# ESP8266-ILI9341-V003_2.net
KiCad netlist of a schematic drawn in EAGLE
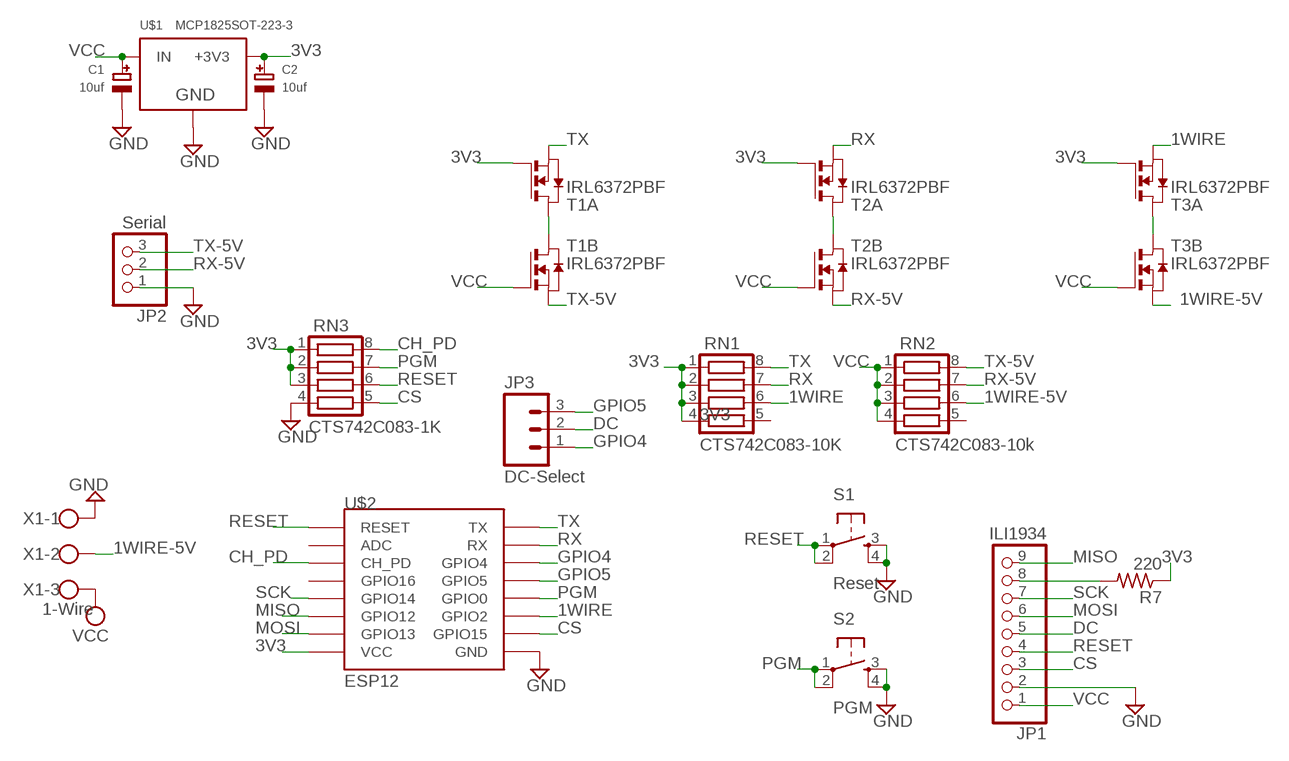
[diagram p0: schematic, sheet 1]

(export (version "E")
  (design (tool "Eeschema 10.0.6"))
  (components
    (comp (ref "C1")
      (value "10uf")
      (footprint "eagle-import:EIA3216-18_A-R")
      (libsource (lib "eagle-import") (part "CAP_TANTALUMA/3216_REFLOW"))
    )
    (comp (ref "C2")
      (value "10uf")
      (footprint "eagle-import:EIA3216-18_A-R")
      (libsource (lib "eagle-import") (part "CAP_TANTALUMA/3216_REFLOW"))
    )
    (comp (ref "JP1")
      (value "ILI1934")
      (footprint "eagle-import:1X09-BIG")
      (libsource (lib "eagle-import") (part "PINHD-1X9"))
    )
    (comp (ref "JP2")
      (value "Serial")
      (footprint "eagle-import:1X03")
      (libsource (lib "eagle-import") (part "PINHD-1X3"))
    )
    (comp (ref "JP3")
      (value "DC-Select")
      (footprint "eagle-import:1X03")
      (libsource (lib "eagle-import") (part "M03PTH"))
    )
    (comp (ref "R7")
      (value "220")
      (footprint "eagle-import:M1206")
      (libsource (lib "eagle-import") (part "R-US_M1206"))
    )
    (comp (ref "RN1")
      (value "CTS742C083-10K")
      (footprint "eagle-import:CTS742C083")
      (libsource (lib "eagle-import") (part "CTS742C083"))
    )
    (comp (ref "RN2")
      (value "CTS742C083-10k")
      (footprint "eagle-import:CTS742C083")
      (libsource (lib "eagle-import") (part "CTS742C083"))
    )
    (comp (ref "RN3")
      (value "CTS742C083-1K")
      (footprint "eagle-import:CTS742C083")
      (libsource (lib "eagle-import") (part "CTS742C083"))
    )
    (comp (ref "S1")
      (value "Reset")
      (footprint "eagle-import:TACTILE-PTH")
      (libsource (lib "eagle-import") (part "TAC_SWITCHPTH"))
    )
    (comp (ref "S2")
      (value "PGM")
      (footprint "eagle-import:TACTILE-PTH")
      (libsource (lib "eagle-import") (part "TAC_SWITCHPTH"))
    )
    (comp (ref "T1")
      (value "IRL6372PBF")
      (footprint "eagle-import:SO-8-DUAL")
      (libsource (lib "eagle-import") (part "IRL6372PBF"))
    )
    (comp (ref "T2")
      (value "IRL6372PBF")
      (footprint "eagle-import:SO-8-DUAL")
      (libsource (lib "eagle-import") (part "IRL6372PBF"))
    )
    (comp (ref "T3")
      (value "IRL6372PBF")
      (footprint "eagle-import:SO-8-DUAL")
      (libsource (lib "eagle-import") (part "IRL6372PBF"))
    )
    (comp (ref "U$1")
      (value "MCP1825SOT-223-3")
      (footprint "eagle-import:SOT-223")
      (libsource (lib "eagle-import") (part "MCP1825SOT-223-3"))
    )
    (comp (ref "U$2")
      (value "ESP12")
      (footprint "eagle-import:ESP12")
      (libsource (lib "eagle-import") (part "ESP12"))
    )
    (comp (ref "X1")
      (value "1-Wire")
      (footprint "eagle-import:W237-103")
      (fields (field (name "MPN") "237-103"))
      (libsource (lib "eagle-import") (part "W237-103"))
    )
  )
  (nets
    (net (code "1") (name "/1WIRE") (class "Default")
      (node (ref "RN1") (pin "6") (pinfunction "6_6") (pintype "passive"))
      (node (ref "T3") (pin "1") (pinfunction "S_1") (pintype "passive"))
      (node (ref "U$2") (pin "GPIO2") (pinfunction "GPIO2_GPIO2") (pintype "bidirectional"))
    )
    (net (code "2") (name "/1WIRE-5V") (class "Default")
      (node (ref "RN2") (pin "6") (pinfunction "6_6") (pintype "passive"))
      (node (ref "T3") (pin "3") (pinfunction "S_3") (pintype "passive"))
      (node (ref "X1") (pin "2") (pinfunction "KL_2") (pintype "passive"))
    )
    (net (code "3") (name "/3V3") (class "Default")
      (node (ref "C2") (pin "+") (pinfunction "+_+") (pintype "passive"))
      (node (ref "R7") (pin "1") (pinfunction "1_1") (pintype "passive"))
      (node (ref "RN1") (pin "1") (pinfunction "1_1") (pintype "passive"))
      (node (ref "RN1") (pin "2") (pinfunction "2_2") (pintype "passive"))
      (node (ref "RN1") (pin "3") (pinfunction "3_3") (pintype "passive"))
      (node (ref "RN1") (pin "4") (pinfunction "4_4") (pintype "passive"))
      (node (ref "RN3") (pin "1") (pinfunction "1_1") (pintype "passive"))
      (node (ref "RN3") (pin "2") (pinfunction "2_2") (pintype "passive"))
      (node (ref "RN3") (pin "3") (pinfunction "3_3") (pintype "passive"))
      (node (ref "T1") (pin "2") (pinfunction "G_2") (pintype "passive"))
      (node (ref "T2") (pin "2") (pinfunction "G_2") (pintype "passive"))
      (node (ref "T3") (pin "2") (pinfunction "G_2") (pintype "passive"))
      (node (ref "U$1") (pin "3") (pinfunction "+3V3_3") (pintype "power_in"))
      (node (ref "U$2") (pin "VCC") (pinfunction "VCC_VCC") (pintype "bidirectional"))
    )
    (net (code "4") (name "/CH_PD") (class "Default")
      (node (ref "RN3") (pin "8") (pinfunction "8_8") (pintype "passive"))
      (node (ref "U$2") (pin "CH_PD") (pinfunction "CH_PD_CH_PD") (pintype "bidirectional"))
    )
    (net (code "5") (name "/CS") (class "Default")
      (node (ref "JP1") (pin "3") (pinfunction "3_3") (pintype "passive"))
      (node (ref "RN3") (pin "5") (pinfunction "5_5") (pintype "passive"))
      (node (ref "U$2") (pin "GPIO15") (pinfunction "GPIO15_GPIO15") (pintype "bidirectional"))
    )
    (net (code "6") (name "/DC") (class "Default")
      (node (ref "JP1") (pin "5") (pinfunction "5_5") (pintype "passive"))
      (node (ref "JP3") (pin "2") (pinfunction "2_2") (pintype "passive"))
    )
    (net (code "7") (name "/GPIO4") (class "Default")
      (node (ref "JP3") (pin "1") (pinfunction "1_1") (pintype "passive"))
      (node (ref "U$2") (pin "GPIO4") (pinfunction "GPIO4_GPIO4") (pintype "bidirectional"))
    )
    (net (code "8") (name "/GPIO5") (class "Default")
      (node (ref "JP3") (pin "3") (pinfunction "3_3") (pintype "passive"))
      (node (ref "U$2") (pin "GPIO5") (pinfunction "GPIO5_GPIO5") (pintype "bidirectional"))
    )
    (net (code "9") (name "/MISO") (class "Default")
      (node (ref "JP1") (pin "9") (pinfunction "9_9") (pintype "passive"))
      (node (ref "U$2") (pin "GPIO12") (pinfunction "GPIO12_GPIO12") (pintype "bidirectional"))
    )
    (net (code "10") (name "/MOSI") (class "Default")
      (node (ref "JP1") (pin "6") (pinfunction "6_6") (pintype "passive"))
      (node (ref "U$2") (pin "GPIO13") (pinfunction "GPIO13_GPIO13") (pintype "bidirectional"))
    )
    (net (code "11") (name "/PGM") (class "Default")
      (node (ref "RN3") (pin "7") (pinfunction "7_7") (pintype "passive"))
      (node (ref "S2") (pin "1") (pinfunction "1_1") (pintype "passive"))
      (node (ref "S2") (pin "2") (pinfunction "2_2") (pintype "passive"))
      (node (ref "U$2") (pin "GPIO0") (pinfunction "GPIO0_GPIO0") (pintype "bidirectional"))
    )
    (net (code "12") (name "/RESET") (class "Default")
      (node (ref "JP1") (pin "4") (pinfunction "4_4") (pintype "passive"))
      (node (ref "RN3") (pin "6") (pinfunction "6_6") (pintype "passive"))
      (node (ref "S1") (pin "1") (pinfunction "1_1") (pintype "passive"))
      (node (ref "S1") (pin "2") (pinfunction "2_2") (pintype "passive"))
      (node (ref "U$2") (pin "RESET") (pinfunction "RESET_RESET") (pintype "bidirectional"))
    )
    (net (code "13") (name "/RX") (class "Default")
      (node (ref "RN1") (pin "7") (pinfunction "7_7") (pintype "passive"))
      (node (ref "T2") (pin "1") (pinfunction "S_1") (pintype "passive"))
      (node (ref "U$2") (pin "RX") (pinfunction "RX_RX") (pintype "bidirectional"))
    )
    (net (code "14") (name "/RX-5V") (class "Default")
      (node (ref "JP2") (pin "2") (pinfunction "2_2") (pintype "passive"))
      (node (ref "RN2") (pin "7") (pinfunction "7_7") (pintype "passive"))
      (node (ref "T2") (pin "3") (pinfunction "S_3") (pintype "passive"))
    )
    (net (code "15") (name "/SCK") (class "Default")
      (node (ref "JP1") (pin "7") (pinfunction "7_7") (pintype "passive"))
      (node (ref "U$2") (pin "GPIO14") (pinfunction "GPIO14_GPIO14") (pintype "bidirectional"))
    )
    (net (code "16") (name "/TX") (class "Default")
      (node (ref "RN1") (pin "8") (pinfunction "8_8") (pintype "passive"))
      (node (ref "T1") (pin "1") (pinfunction "S_1") (pintype "passive"))
      (node (ref "U$2") (pin "TX") (pinfunction "TX_TX") (pintype "bidirectional"))
    )
    (net (code "17") (name "/TX-5V") (class "Default")
      (node (ref "JP2") (pin "3") (pinfunction "3_3") (pintype "passive"))
      (node (ref "RN2") (pin "8") (pinfunction "8_8") (pintype "passive"))
      (node (ref "T1") (pin "3") (pinfunction "S_3") (pintype "passive"))
    )
    (net (code "18") (name "GND") (class "Default")
      (node (ref "C1") (pin "-") (pinfunction "-_-") (pintype "passive"))
      (node (ref "C2") (pin "-") (pinfunction "-_-") (pintype "passive"))
      (node (ref "JP1") (pin "2") (pinfunction "2_2") (pintype "passive"))
      (node (ref "JP2") (pin "1") (pinfunction "1_1") (pintype "passive"))
      (node (ref "RN3") (pin "4") (pinfunction "4_4") (pintype "passive"))
      (node (ref "S1") (pin "3") (pinfunction "3_3") (pintype "passive"))
      (node (ref "S1") (pin "4") (pinfunction "4_4") (pintype "passive"))
      (node (ref "S2") (pin "3") (pinfunction "3_3") (pintype "passive"))
      (node (ref "S2") (pin "4") (pinfunction "4_4") (pintype "passive"))
      (node (ref "U$1") (pin "2") (pinfunction "GND_2") (pintype "power_in"))
      (node (ref "U$2") (pin "GND") (pinfunction "GND_GND") (pintype "bidirectional"))
      (node (ref "X1") (pin "1") (pinfunction "KL_1") (pintype "passive"))
    )
    (net (code "19") (name "Net-(JP1-Pad8)") (class "Default")
      (node (ref "JP1") (pin "8") (pinfunction "8_8") (pintype "passive"))
      (node (ref "R7") (pin "2") (pinfunction "2_2") (pintype "passive"))
    )
    (net (code "20") (name "Net-(T1A-D)") (class "Default")
      (node (ref "T1") (pin "5_6") (pinfunction "D_5_6") (pintype "passive"))
      (node (ref "T1") (pin "7_8") (pinfunction "D_7_8") (pintype "passive"))
    )
    (net (code "21") (name "Net-(T2A-D)") (class "Default")
      (node (ref "T2") (pin "5_6") (pinfunction "D_5_6") (pintype "passive"))
      (node (ref "T2") (pin "7_8") (pinfunction "D_7_8") (pintype "passive"))
    )
    (net (code "22") (name "Net-(T3A-D)") (class "Default")
      (node (ref "T3") (pin "5_6") (pinfunction "D_5_6") (pintype "passive"))
      (node (ref "T3") (pin "7_8") (pinfunction "D_7_8") (pintype "passive"))
    )
    (net (code "23") (name "VCC") (class "Default")
      (node (ref "C1") (pin "+") (pinfunction "+_+") (pintype "passive"))
      (node (ref "JP1") (pin "1") (pinfunction "1_1") (pintype "passive"))
      (node (ref "RN2") (pin "1") (pinfunction "1_1") (pintype "passive"))
      (node (ref "RN2") (pin "2") (pinfunction "2_2") (pintype "passive"))
      (node (ref "RN2") (pin "3") (pinfunction "3_3") (pintype "passive"))
      (node (ref "RN2") (pin "4") (pinfunction "4_4") (pintype "passive"))
      (node (ref "T1") (pin "4") (pinfunction "G_4") (pintype "passive"))
      (node (ref "T2") (pin "4") (pinfunction "G_4") (pintype "passive"))
      (node (ref "T3") (pin "4") (pinfunction "G_4") (pintype "passive"))
      (node (ref "U$1") (pin "1") (pinfunction "IN_1") (pintype "power_in"))
      (node (ref "X1") (pin "3") (pinfunction "KL_3") (pintype "passive"))
    )
    (net (code "24") (name "unconnected-(RN1-Pad5)") (class "Default")
      (node (ref "RN1") (pin "5") (pinfunction "5_5") (pintype "passive"))
    )
    (net (code "25") (name "unconnected-(RN2-Pad5)") (class "Default")
      (node (ref "RN2") (pin "5") (pinfunction "5_5") (pintype "passive"))
    )
    (net (code "26") (name "unconnected-(U$2-PadADC)") (class "Default")
      (node (ref "U$2") (pin "ADC") (pinfunction "ADC_ADC") (pintype "bidirectional"))
    )
    (net (code "27") (name "unconnected-(U$2-PadGPIO16)") (class "Default")
      (node (ref "U$2") (pin "GPIO16") (pinfunction "GPIO16_GPIO16") (pintype "bidirectional"))
    )
  )
)
